# sustentationAvecPC.net
KiCad netlist of a schematic drawn in Altium Designer
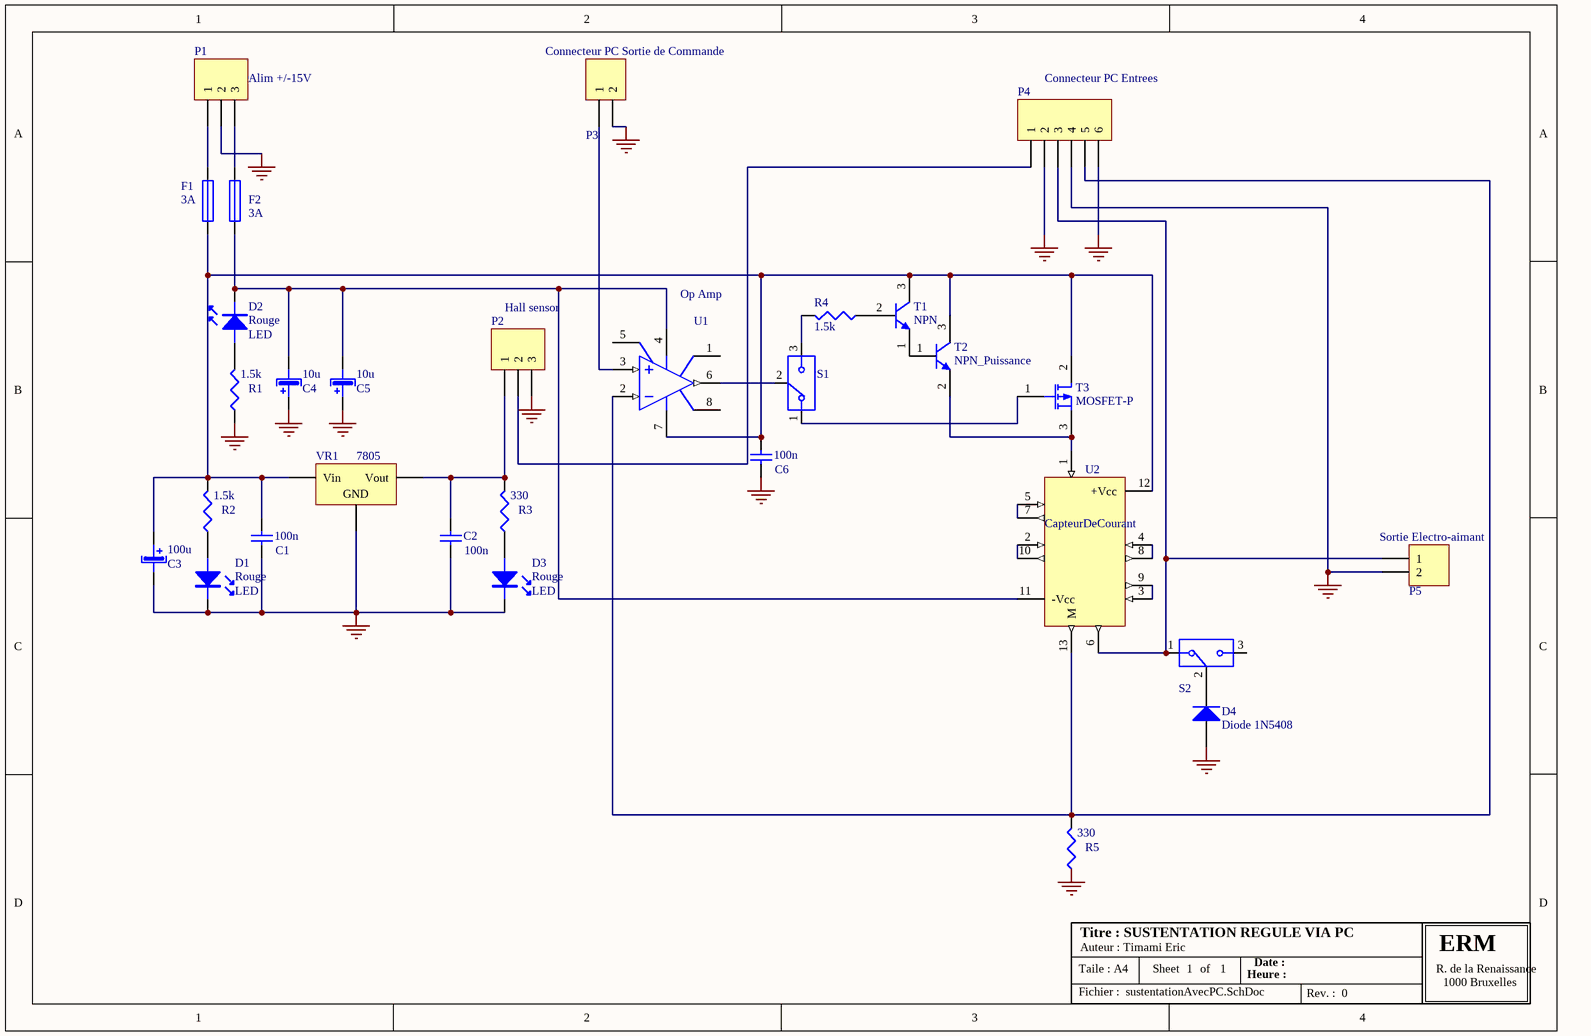
[diagram p0: sustentationAvecPC.SchDoc]

(export (version "E")
  (design (tool "Eeschema 10.0.6"))
  (components
    (comp (ref "C1")
      (value "100n")
      (footprint "Capa_100n")
      (description "Condensateur")
      (fields (field (name "DESIGNER") "ECAM 2004"))
      (libsource (lib "AntiNuisibles") (part "Condensateur"))
    )
    (comp (ref "C2")
      (value "100n")
      (footprint "Capa_100n")
      (description "Condensateur")
      (fields (field (name "DESIGNER") "ECAM 2004"))
      (libsource (lib "sustentationAvecPC") (part "Condensateur"))
    )
    (comp (ref "C3")
      (value "100u")
      (footprint "AXIAL-1.0")
      (description "Condensateur polatisé")
      (fields (field (name "Comment") "Cond pol radial") (field (name "DESIGNER") "ECAM 2004"))
      (libsource (lib "sustentationAvecPC") (part "Cond pol radial"))
    )
    (comp (ref "C4")
      (value "10u")
      (footprint "CAPPR_100u")
      (description "Condensateur polatisé")
      (fields (field (name "Comment") "Cond pol radial") (field (name "DESIGNER") "ECAM 2004"))
      (libsource (lib "sustentationAvecPC") (part "Cond pol radial"))
    )
    (comp (ref "C5")
      (value "10u")
      (footprint "CAPPR_100u")
      (description "Condensateur polatisé")
      (fields (field (name "Comment") "Cond pol  rad") (field (name "DESIGNER") "ECAM 2004"))
      (libsource (lib "sustentationAvecPC") (part "Cond pol radial"))
    )
    (comp (ref "C6")
      (value "100n")
      (footprint "Capa_100n")
      (description "Condensateur")
      (fields (field (name "DESIGNER") "ECAM 2004"))
      (libsource (lib "sustentationAvecPC") (part "Condensateur"))
    )
    (comp (ref "D1")
      (value "LED")
      (footprint "Led 0.1")
      (fields (field (name "COLOR") "Rouge") (field (name "DESIGNER") "ECAM 2004"))
      (libsource (lib "sustentationAvecPC") (part "LED"))
    )
    (comp (ref "D2")
      (value "LED")
      (footprint "Led 0.1")
      (fields (field (name "COLOR") "Rouge") (field (name "DESIGNER") "ECAM 2004"))
      (libsource (lib "sustentationAvecPC") (part "LED"))
    )
    (comp (ref "D3")
      (value "LED")
      (footprint "Led 0.1")
      (fields (field (name "COLOR") "Rouge") (field (name "DESIGNER") "ECAM 2004"))
      (libsource (lib "sustentationAvecPC") (part "LED"))
    )
    (comp (ref "D4")
      (value "Diode 1N5408")
      (footprint "DIODE-1N5408")
      (description "3 Amp Medium Power Silicon Rectifier Diode")
      (fields (field (name "PUBLISHER") "Altium Limited"))
      (libsource (lib "sustentationAvecPC") (part "Diode 1N5408"))
    )
    (comp (ref "F1")
      (value "3A")
      (footprint "FUSE-10")
      (description "Fusible")
      (fields (field (name "DESIGNER") "ECAM 2004"))
      (libsource (lib "*") (part "Fusible"))
    )
    (comp (ref "F2")
      (value "3A")
      (footprint "FUSE-10")
      (description "Fusible")
      (fields (field (name "DESIGNER") "ECAM 2004"))
      (libsource (lib "*") (part "Fusible"))
    )
    (comp (ref "P1")
      (value "Alim +/-15V")
      (footprint "CONVIS-3")
      (description "Header, 3-Pin")
      (fields (field (name "PUBLISHER") "Altium Limited"))
      (libsource (lib "sustentationAvecPC") (part "connecteur 3"))
    )
    (comp (ref "P2")
      (value "Hall sensor")
      (footprint "connecteur capteur Hall")
      (description "Header, 3-Pin")
      (fields (field (name "PUBLISHER") "Altium Limited"))
      (libsource (lib "sustentationAvecPC") (part "connecteur 3"))
    )
    (comp (ref "P3")
      (value "Connecteur PC Sortie de Commande")
      (footprint "connecteur PC Sorties command")
      (description "Connecteur")
      (fields (field (name "DESIGNER") "ECAM 2005"))
      (libsource (lib "sustentationAvecPC") (part "Connecteur 2"))
    )
    (comp (ref "P4")
      (value "Connecteur PC Entrees")
      (footprint "connecteur PC Entrées")
      (description "Header, 6-Pin")
      (fields (field (name "PUBLISHER") "Altium Limited"))
      (libsource (lib "sustentationAvecPC") (part "Header 6"))
    )
    (comp (ref "P5")
      (value "Sortie Electro-aimant")
      (footprint "connecteur 3A")
      (description "Connecteur")
      (fields (field (name "DESIGNER") "ECAM 2005"))
      (libsource (lib "") (part "Connecteur 2_1"))
    )
    (comp (ref "R1")
      (value "1.5k")
      (footprint "AXIAL-0.4")
      (description "Résistance standard")
      (fields (field (name "Comment") "Résistance") (field (name "DESIGNER") "ECAM 2005"))
      (libsource (lib "sustentationAvecPC") (part "Résistance"))
    )
    (comp (ref "R2")
      (value "1.5k")
      (footprint "AXIAL-0.4")
      (description "Résistance standard")
      (fields (field (name "Comment") "Résistance") (field (name "DESIGNER") "ECAM 2005"))
      (libsource (lib "sustentationAvecPC") (part "Résistance"))
    )
    (comp (ref "R3")
      (value "330")
      (footprint "AXIAL-0.4")
      (description "Résistance standard")
      (fields (field (name "Comment") "Résistance") (field (name "DESIGNER") "ECAM 2005"))
      (libsource (lib "sustentationAvecPC") (part "Résistance"))
    )
    (comp (ref "R4")
      (value "1.5k")
      (footprint "AXIAL-0.4")
      (description "Résistance standard")
      (fields (field (name "Comment") "Résistance") (field (name "DESIGNER") "ECAM 2005"))
      (libsource (lib "sustentationAvecPC") (part "Résistance"))
    )
    (comp (ref "R5")
      (value "330")
      (footprint "AXIAL-0.4")
      (description "Résistance standard")
      (fields (field (name "Comment") "Résistance") (field (name "DESIGNER") "ECAM 2005"))
      (libsource (lib "sustentationAvecPC") (part "Résistance"))
    )
    (comp (ref "S1")
      (value "DIP Inverseur")
      (footprint "SIP3")
      (description "Inverseur")
      (fields (field (name "DESIGNER") "ECAM 2003"))
      (libsource (lib "AntiNuisibles") (part "DIP Inverseur"))
    )
    (comp (ref "S2")
      (value "DIP Inverseur")
      (footprint "SIP3")
      (description "Inverseur")
      (fields (field (name "DESIGNER") "ECAM 2003"))
      (libsource (lib "sustentationAvecPC") (part "DIP Inverseur"))
    )
    (comp (ref "T1")
      (value "NPN")
      (footprint "TO-5")
      (description "NPN Bipolar Transistor")
      (fields (field (name "PUBLISHER") "Altium Limited"))
      (libsource (lib "sustentationAvecPC") (part "NPN"))
    )
    (comp (ref "T2")
      (value "NPN_Puissance")
      (footprint "TO-3")
      (description "NPN Bipolar Transistor")
      (fields (field (name "PUBLISHER") "Altium Limited"))
      (libsource (lib "sustentationAvecPC") (part "NPN_Puissance"))
    )
    (comp (ref "T3")
      (value "MOSFET-P")
      (footprint "TO-220 - Transistor")
      (description "P-Channel MOSFET")
      (fields (field (name "PUBLISHER") "Altium Limited"))
      (libsource (lib "sustentationAvecPC") (part "MOSFET-P"))
    )
    (comp (ref "U1")
      (value "Op Amp")
      (footprint "DIP8")
      (description "FET Operational Amplifier")
      (fields (field (name "PUBLISHER") "Altium Limited"))
      (libsource (lib "sustentationAvecPC") (part "Op Amp"))
    )
    (comp (ref "U2")
      (value "CapteurDeCourant")
      (footprint "Sonde_Courant")
      (fields (field (name "PUBLISHER") "Altium Limited"))
      (libsource (lib "sustentationAvecPC") (part "CapteurDeCourant"))
    )
    (comp (ref "VR1")
      (value "7805")
      (footprint "TO-220 regulateur")
      (description "Voltage Regulator")
      (fields (field (name "PUBLISHER") "Altium Limited"))
      (libsource (lib "sustentationAvecPC") (part "Volt Reg"))
    )
  )
  (nets
    (net (code "1") (name "GND") (class "Default")
      (node (ref "C1") (pin "2") (pinfunction "2_2") (pintype "passive"))
      (node (ref "C2") (pin "2") (pinfunction "2_2") (pintype "passive"))
      (node (ref "C3") (pin "2") (pinfunction "-_2") (pintype "passive"))
      (node (ref "C4") (pin "1") (pinfunction "+_1") (pintype "passive"))
      (node (ref "C5") (pin "1") (pinfunction "+_1") (pintype "passive"))
      (node (ref "C6") (pin "2") (pinfunction "2_2") (pintype "passive"))
      (node (ref "D1") (pin "2") (pinfunction "K_2") (pintype "passive"))
      (node (ref "D3") (pin "2") (pinfunction "K_2") (pintype "passive"))
      (node (ref "D4") (pin "1") (pinfunction "A_1") (pintype "passive"))
      (node (ref "P1") (pin "2") (pinfunction "2_2") (pintype "passive"))
      (node (ref "P2") (pin "3") (pinfunction "3_3") (pintype "passive"))
      (node (ref "P3") (pin "2") (pinfunction "2_2") (pintype "passive"))
      (node (ref "P4") (pin "2") (pinfunction "2_2") (pintype "passive"))
      (node (ref "P4") (pin "4") (pinfunction "4_4") (pintype "passive"))
      (node (ref "P4") (pin "6") (pinfunction "6_6") (pintype "passive"))
      (node (ref "P5") (pin "2") (pinfunction "2_2") (pintype "passive"))
      (node (ref "R1") (pin "1") (pinfunction "1_1") (pintype "passive"))
      (node (ref "VR1") (pin "2") (pinfunction "GND_2") (pintype "passive"))
    )
    (net (code "2") (name "Net-(C3-+)") (class "Default")
      (node (ref "C1") (pin "1") (pinfunction "1_1") (pintype "passive"))
      (node (ref "C3") (pin "1") (pinfunction "+_1") (pintype "passive"))
      (node (ref "C6") (pin "1") (pinfunction "1_1") (pintype "passive"))
      (node (ref "F1") (pin "2") (pinfunction "F2_2") (pintype "passive"))
      (node (ref "R2") (pin "2") (pinfunction "2_2") (pintype "passive"))
      (node (ref "T1") (pin "3") (pinfunction "C_3") (pintype "passive"))
      (node (ref "T2") (pin "3") (pinfunction "C_3") (pintype "passive"))
      (node (ref "T3") (pin "2") (pinfunction "D_2") (pintype "passive"))
      (node (ref "U1") (pin "7") (pinfunction "V+_7") (pintype "power_in"))
      (node (ref "U2") (pin "12") (pinfunction "+Vcc_12") (pintype "power_in"))
      (node (ref "VR1") (pin "1") (pinfunction "Vin_1") (pintype "passive"))
    )
    (net (code "3") (name "Net-(C4--)") (class "Default")
      (node (ref "C4") (pin "2") (pinfunction "-_2") (pintype "passive"))
      (node (ref "C5") (pin "2") (pinfunction "-_2") (pintype "passive"))
      (node (ref "D2") (pin "2") (pinfunction "K_2") (pintype "passive"))
      (node (ref "F2") (pin "2") (pinfunction "F2_2") (pintype "passive"))
      (node (ref "U1") (pin "4") (pinfunction "V-_4") (pintype "power_in"))
      (node (ref "U2") (pin "11") (pinfunction "-Vcc_11") (pintype "power_in"))
    )
    (net (code "4") (name "Net-(D1-A)") (class "Default")
      (node (ref "D1") (pin "1") (pinfunction "A_1") (pintype "passive"))
      (node (ref "R2") (pin "1") (pinfunction "1_1") (pintype "passive"))
    )
    (net (code "5") (name "Net-(D2-A)") (class "Default")
      (node (ref "D2") (pin "1") (pinfunction "A_1") (pintype "passive"))
      (node (ref "R1") (pin "2") (pinfunction "2_2") (pintype "passive"))
    )
    (net (code "6") (name "Net-(D3-A)") (class "Default")
      (node (ref "D3") (pin "1") (pinfunction "A_1") (pintype "passive"))
      (node (ref "R3") (pin "1") (pinfunction "1_1") (pintype "passive"))
    )
    (net (code "7") (name "Net-(D4-K)") (class "Default")
      (node (ref "D4") (pin "2") (pinfunction "K_2") (pintype "passive"))
      (node (ref "S2") (pin "2") (pinfunction "COM_2") (pintype "passive"))
    )
    (net (code "8") (name "Net-(F1-F1)") (class "Default")
      (node (ref "F1") (pin "1") (pinfunction "F1_1") (pintype "passive"))
      (node (ref "P1") (pin "1") (pinfunction "1_1") (pintype "passive"))
    )
    (net (code "9") (name "Net-(F2-F1)") (class "Default")
      (node (ref "F2") (pin "1") (pinfunction "F1_1") (pintype "passive"))
      (node (ref "P1") (pin "3") (pinfunction "3_3") (pintype "passive"))
    )
    (net (code "10") (name "Net-(P2-Pad2)") (class "Default")
      (node (ref "P2") (pin "2") (pinfunction "2_2") (pintype "passive"))
      (node (ref "P4") (pin "1") (pinfunction "1_1") (pintype "passive"))
    )
    (net (code "11") (name "Net-(S1-COM)") (class "Default")
      (node (ref "S1") (pin "2") (pinfunction "COM_2") (pintype "passive"))
      (node (ref "U1") (pin "6") (pinfunction "OUT_6") (pintype "output"))
    )
    (net (code "12") (name "Net-(S1-TA)") (class "Default")
      (node (ref "S1") (pin "1") (pinfunction "TA_1") (pintype "passive"))
      (node (ref "T3") (pin "1") (pinfunction "G_1") (pintype "passive"))
    )
    (net (code "13") (name "Net-(S1-TB)") (class "Default")
      (node (ref "R4") (pin "2") (pinfunction "2_2") (pintype "passive"))
      (node (ref "S1") (pin "3") (pinfunction "TB_3") (pintype "passive"))
    )
    (net (code "14") (name "Net-(S2-TA)") (class "Default")
      (node (ref "P4") (pin "3") (pinfunction "3_3") (pintype "passive"))
      (node (ref "P5") (pin "1") (pinfunction "1_1") (pintype "passive"))
      (node (ref "S2") (pin "1") (pinfunction "TA_1") (pintype "passive"))
      (node (ref "U2") (pin "6") (pintype "output"))
    )
    (net (code "15") (name "Net-(T1-B)") (class "Default")
      (node (ref "R4") (pin "1") (pinfunction "1_1") (pintype "passive"))
      (node (ref "T1") (pin "2") (pinfunction "B_2") (pintype "passive"))
    )
    (net (code "16") (name "Net-(T1-E)") (class "Default")
      (node (ref "T1") (pin "1") (pinfunction "E_1") (pintype "passive"))
      (node (ref "T2") (pin "1") (pinfunction "B_1") (pintype "passive"))
    )
    (net (code "17") (name "Net-(T2-E)") (class "Default")
      (node (ref "T2") (pin "2") (pinfunction "E_2") (pintype "passive"))
      (node (ref "T3") (pin "3") (pinfunction "S_3") (pintype "passive"))
      (node (ref "U2") (pin "1") (pintype "input"))
    )
    (net (code "18") (name "Net-(U1-IN+)") (class "Default")
      (node (ref "P3") (pin "1") (pinfunction "1_1") (pintype "passive"))
      (node (ref "U1") (pin "3") (pinfunction "IN+_3") (pintype "input"))
    )
    (net (code "19") (name "Net-(U1-IN-)") (class "Default")
      (node (ref "P4") (pin "5") (pinfunction "5_5") (pintype "passive"))
      (node (ref "R5") (pin "2") (pinfunction "2_2") (pintype "passive"))
      (node (ref "U1") (pin "2") (pinfunction "IN-_2") (pintype "input"))
      (node (ref "U2") (pin "13") (pinfunction "M_13") (pintype "output"))
    )
    (net (code "20") (name "Net-(U2-Pad3)") (class "Default")
      (node (ref "U2") (pin "3") (pintype "input"))
      (node (ref "U2") (pin "9") (pintype "output"))
    )
    (net (code "21") (name "Net-(U2-Pad4)") (class "Default")
      (node (ref "U2") (pin "4") (pintype "input"))
      (node (ref "U2") (pin "8") (pintype "output"))
    )
    (net (code "22") (name "Net-(U2-Pad5)") (class "Default")
      (node (ref "U2") (pin "5") (pintype "input"))
      (node (ref "U2") (pin "7") (pintype "output"))
    )
    (net (code "23") (name "Net-(U2-Pad10)") (class "Default")
      (node (ref "U2") (pin "10") (pintype "output"))
      (node (ref "U2") (pin "2") (pintype "input"))
    )
    (net (code "24") (name "Net-(VR1-Vout)") (class "Default")
      (node (ref "C2") (pin "1") (pinfunction "1_1") (pintype "passive"))
      (node (ref "P2") (pin "1") (pinfunction "1_1") (pintype "passive"))
      (node (ref "R3") (pin "2") (pinfunction "2_2") (pintype "passive"))
      (node (ref "VR1") (pin "3") (pinfunction "Vout_3") (pintype "passive"))
    )
    (net (code "25") (name "unconnected-(R5-Pad1)") (class "Default")
      (node (ref "R5") (pin "1") (pinfunction "1_1") (pintype "passive"))
    )
    (net (code "26") (name "unconnected-(S2-TB-Pad3)") (class "Default")
      (node (ref "S2") (pin "3") (pinfunction "TB_3") (pintype "passive"))
    )
    (net (code "27") (name "unconnected-(U1-OS_NUL-Pad1)") (class "Default")
      (node (ref "U1") (pin "1") (pinfunction "OS_NUL_1") (pintype "passive"))
    )
    (net (code "28") (name "unconnected-(U1-OS_NUL-Pad5)") (class "Default")
      (node (ref "U1") (pin "5") (pinfunction "OS_NUL_5") (pintype "passive"))
    )
    (net (code "29") (name "unconnected-(U1-TAB-Pad8)") (class "Default")
      (node (ref "U1") (pin "8") (pinfunction "TAB_8") (pintype "passive"))
    )
  )
)
